# small.net
KiCad netlist of a schematic drawn in EAGLE
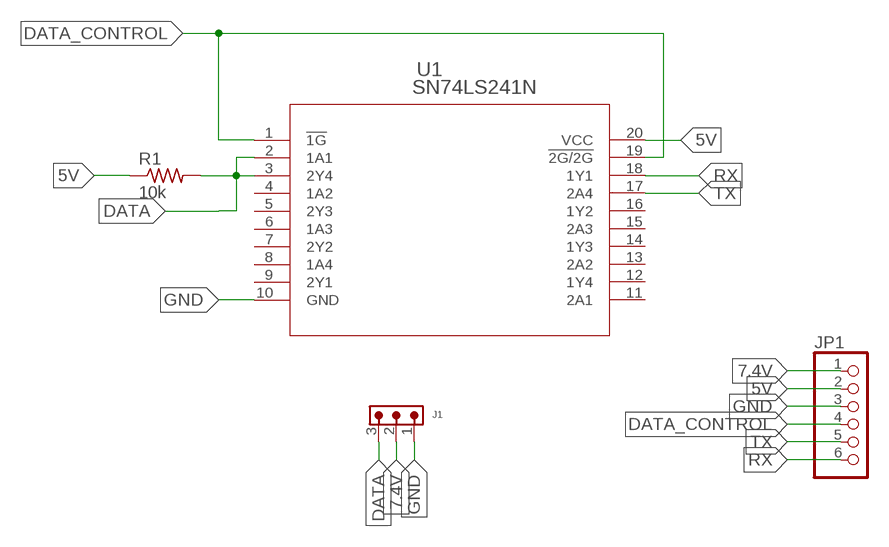
[diagram p0: schematic, sheet 1]

(export (version "E")
  (design (tool "Eeschema 10.0.6"))
  (components
    (comp (ref "J1")
      (value "62000311622")
      (footprint "eagle-import:62000311622")
      (libsource (lib "eagle-import") (part "62000311622"))
    )
    (comp (ref "JP1")
      (value "PINHD-1X6")
      (footprint "eagle-import:1X06")
      (libsource (lib "eagle-import") (part "PINHD-1X6"))
    )
    (comp (ref "R1")
      (value "10k")
      (footprint "eagle-import:M0805")
      (libsource (lib "eagle-import") (part "R-US_M0805"))
    )
    (comp (ref "U1")
      (value "SN74LS241N")
      (footprint "eagle-import:N20")
      (libsource (lib "eagle-import") (part "SN74LS241N"))
    )
  )
  (nets
    (net (code "1") (name "5V") (class "Default")
      (node (ref "JP1") (pin "2") (pinfunction "2_2") (pintype "passive"))
      (node (ref "R1") (pin "1") (pinfunction "1_1") (pintype "passive"))
      (node (ref "U1") (pin "20") (pinfunction "VCC_20") (pintype "power_in"))
    )
    (net (code "2") (name "7.4V") (class "Default")
      (node (ref "J1") (pin "2") (pinfunction "2_2") (pintype "passive"))
      (node (ref "JP1") (pin "1") (pinfunction "1_1") (pintype "passive"))
    )
    (net (code "3") (name "DATA") (class "Default")
      (node (ref "J1") (pin "3") (pinfunction "3_3") (pintype "passive"))
      (node (ref "R1") (pin "2") (pinfunction "2_2") (pintype "passive"))
      (node (ref "U1") (pin "2") (pinfunction "1A1_2") (pintype "input"))
      (node (ref "U1") (pin "3") (pinfunction "2Y4_3") (pintype "output"))
    )
    (net (code "4") (name "DATA_CONTROL") (class "Default")
      (node (ref "JP1") (pin "4") (pinfunction "4_4") (pintype "passive"))
      (node (ref "U1") (pin "1") (pinfunction "~{1G}_1") (pintype "input"))
      (node (ref "U1") (pin "19") (pinfunction "~{2G/2G}_19") (pintype "input"))
    )
    (net (code "5") (name "GND") (class "Default")
      (node (ref "J1") (pin "1") (pinfunction "1_1") (pintype "passive"))
      (node (ref "JP1") (pin "3") (pinfunction "3_3") (pintype "passive"))
      (node (ref "U1") (pin "10") (pinfunction "GND_10") (pintype "power_in"))
    )
    (net (code "6") (name "RX") (class "Default")
      (node (ref "JP1") (pin "6") (pinfunction "6_6") (pintype "passive"))
      (node (ref "U1") (pin "18") (pinfunction "1Y1_18") (pintype "output"))
    )
    (net (code "7") (name "TX") (class "Default")
      (node (ref "JP1") (pin "5") (pinfunction "5_5") (pintype "passive"))
      (node (ref "U1") (pin "17") (pinfunction "2A4_17") (pintype "input"))
    )
    (net (code "8") (name "unconnected-(U1-1A2-Pad4)") (class "Default")
      (node (ref "U1") (pin "4") (pinfunction "1A2_4") (pintype "input"))
    )
    (net (code "9") (name "unconnected-(U1-1A3-Pad6)") (class "Default")
      (node (ref "U1") (pin "6") (pinfunction "1A3_6") (pintype "input"))
    )
    (net (code "10") (name "unconnected-(U1-1A4-Pad8)") (class "Default")
      (node (ref "U1") (pin "8") (pinfunction "1A4_8") (pintype "input"))
    )
    (net (code "11") (name "unconnected-(U1-1Y2-Pad16)") (class "Default")
      (node (ref "U1") (pin "16") (pinfunction "1Y2_16") (pintype "output"))
    )
    (net (code "12") (name "unconnected-(U1-1Y3-Pad14)") (class "Default")
      (node (ref "U1") (pin "14") (pinfunction "1Y3_14") (pintype "output"))
    )
    (net (code "13") (name "unconnected-(U1-1Y4-Pad12)") (class "Default")
      (node (ref "U1") (pin "12") (pinfunction "1Y4_12") (pintype "output"))
    )
    (net (code "14") (name "unconnected-(U1-2A1-Pad11)") (class "Default")
      (node (ref "U1") (pin "11") (pinfunction "2A1_11") (pintype "input"))
    )
    (net (code "15") (name "unconnected-(U1-2A2-Pad13)") (class "Default")
      (node (ref "U1") (pin "13") (pinfunction "2A2_13") (pintype "input"))
    )
    (net (code "16") (name "unconnected-(U1-2A3-Pad15)") (class "Default")
      (node (ref "U1") (pin "15") (pinfunction "2A3_15") (pintype "input"))
    )
    (net (code "17") (name "unconnected-(U1-2Y1-Pad9)") (class "Default")
      (node (ref "U1") (pin "9") (pinfunction "2Y1_9") (pintype "output"))
    )
    (net (code "18") (name "unconnected-(U1-2Y2-Pad7)") (class "Default")
      (node (ref "U1") (pin "7") (pinfunction "2Y2_7") (pintype "output"))
    )
    (net (code "19") (name "unconnected-(U1-2Y3-Pad5)") (class "Default")
      (node (ref "U1") (pin "5") (pinfunction "2Y3_5") (pintype "output"))
    )
  )
)
